# gocupi_0_7_0.net
KiCad netlist of a schematic drawn in EAGLE
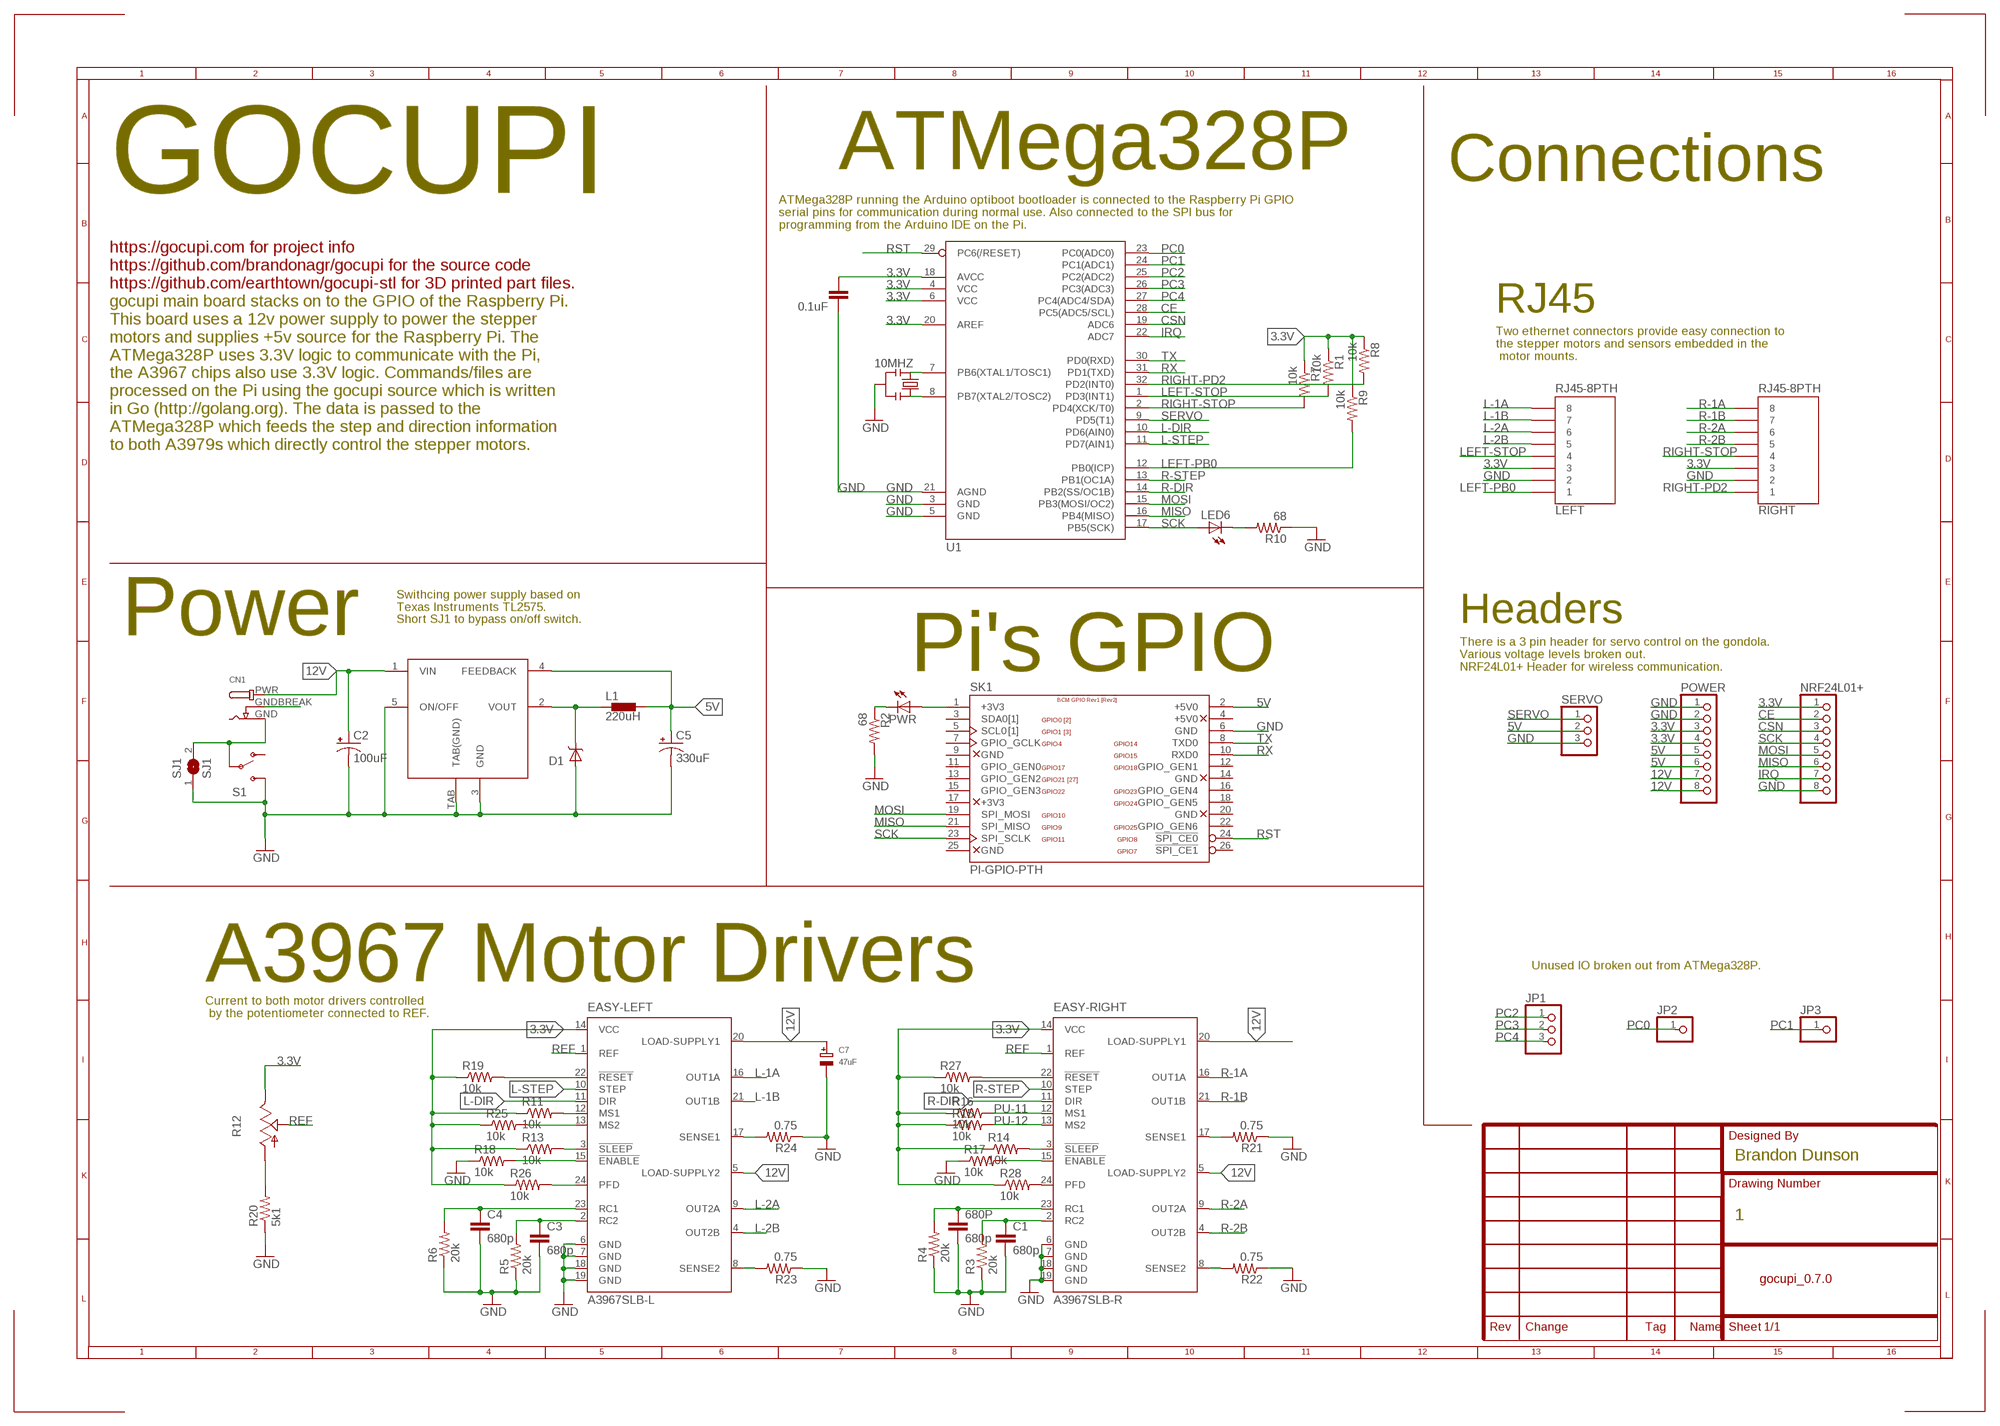
[diagram p0: schematic, sheet 1]

(export (version "E")
  (design (tool "Eeschema 10.0.6"))
  (components
    (comp (ref "10MHZ")
      (value "RESONATORSMD")
      (footprint "eagle-import:RESONATOR-SMD")
      (libsource (lib "eagle-import") (part "RESONATORSMD"))
    )
    (comp (ref "680P")
      (value "680p")
      (footprint "eagle-import:0805")
      (libsource (lib "eagle-import") (part "CAP0805"))
    )
    (comp (ref "C1")
      (value "680p")
      (footprint "eagle-import:0805")
      (libsource (lib "eagle-import") (part "CAP0805"))
    )
    (comp (ref "C2")
      (value "100uF")
      (footprint "eagle-import:PANASONIC_D")
      (libsource (lib "eagle-import") (part "CPOL-USD"))
    )
    (comp (ref "C3")
      (value "680p")
      (footprint "eagle-import:0805")
      (libsource (lib "eagle-import") (part "CAP0805"))
    )
    (comp (ref "C4")
      (value "680p")
      (footprint "eagle-import:0805")
      (libsource (lib "eagle-import") (part "CAP0805"))
    )
    (comp (ref "C5")
      (value "330uF")
      (footprint "eagle-import:PANASONIC_F")
      (libsource (lib "eagle-import") (part "CPOL-USF"))
    )
    (comp (ref "C7")
      (value "47uF")
      (footprint "eagle-import:PANASONIC_C")
      (libsource (lib "eagle-import") (part "CAP_ELECTROLYTICPANASONIC_C"))
    )
    (comp (ref "C8")
      (value "0.1uF")
      (footprint "eagle-import:0805")
      (libsource (lib "eagle-import") (part "CAP0805"))
    )
    (comp (ref "CN1")
      (value "DCBARRELSMT_CORRECT")
      (footprint "eagle-import:DCJACK_2MM_SMT")
      (libsource (lib "eagle-import") (part "DCBARRELSMT_CORRECT"))
    )
    (comp (ref "D1")
      (value "1N5819")
      (footprint "eagle-import:SMA-DIODE")
      (libsource (lib "eagle-import") (part "DIODE-SCHOTTKY_"))
    )
    (comp (ref "EASY-LEFT")
      (value "A3967SLB-L")
      (footprint "eagle-import:SO24W")
      (fields (field (name "MF") "ALLEGRO MICROSYSTEMS, INC.") (field (name "MPN") "A3967SLB-T"))
      (libsource (lib "eagle-import") (part "A3967SLB"))
    )
    (comp (ref "EASY-RIGHT")
      (value "A3967SLB-R")
      (footprint "eagle-import:SO24W")
      (fields (field (name "MF") "ALLEGRO MICROSYSTEMS, INC.") (field (name "MPN") "A3967SLB-T"))
      (libsource (lib "eagle-import") (part "A3967SLB"))
    )
    (comp (ref "JP1")
      (value "PINHD-1X3CB")
      (footprint "eagle-import:1X03-CLEANBIG")
      (libsource (lib "eagle-import") (part "PINHD-1X3CB"))
    )
    (comp (ref "JP2")
      (value "PINHD-1X1CB")
      (footprint "eagle-import:1X01-CLEANBIG")
      (libsource (lib "eagle-import") (part "PINHD-1X1CB"))
    )
    (comp (ref "JP3")
      (value "PINHD-1X1CB")
      (footprint "eagle-import:1X01-CLEANBIG")
      (libsource (lib "eagle-import") (part "PINHD-1X1CB"))
    )
    (comp (ref "L1")
      (value "220uH")
      (footprint "eagle-import:SDR1305")
      (libsource (lib "eagle-import") (part "SDR1305"))
    )
    (comp (ref "LED6")
      (value "LEDCHIPLED_1206")
      (footprint "eagle-import:CHIPLED_1206")
      (libsource (lib "eagle-import") (part "LEDCHIPLED_1206"))
    )
    (comp (ref "LEFT")
      (value "RJ45-8PTH")
      (footprint "eagle-import:RJ45-8")
      (libsource (lib "eagle-import") (part "RJ45-8PTH"))
    )
    (comp (ref "NRF24L01+")
      (value "PINHD-1X8BIG")
      (footprint "eagle-import:1X08-BIG")
      (libsource (lib "eagle-import") (part "PINHD-1X8BIG"))
    )
    (comp (ref "POWER")
      (value "PINHD-1X8CLEANBIG")
      (footprint "eagle-import:1X08-CLEANBIG")
      (libsource (lib "eagle-import") (part "PINHD-1X8CLEANBIG"))
    )
    (comp (ref "PWR")
      (value "LEDCHIPLED_1206")
      (footprint "eagle-import:CHIPLED_1206")
      (libsource (lib "eagle-import") (part "LEDCHIPLED_1206"))
    )
    (comp (ref "R1")
      (value "10k")
      (footprint "eagle-import:0805")
      (libsource (lib "eagle-import") (part "SparkFun-Resistors_RESISTOR0805-RES"))
    )
    (comp (ref "R2")
      (value "68")
      (footprint "eagle-import:0805")
      (libsource (lib "eagle-import") (part "SparkFun-Resistors_RESISTOR0805-RES"))
    )
    (comp (ref "R3")
      (value "20k")
      (footprint "eagle-import:0805")
      (libsource (lib "eagle-import") (part "SparkFun-Resistors_RESISTOR0805-RES"))
    )
    (comp (ref "R4")
      (value "20k")
      (footprint "eagle-import:0805")
      (libsource (lib "eagle-import") (part "SparkFun-Resistors_RESISTOR0805-RES"))
    )
    (comp (ref "R5")
      (value "20k")
      (footprint "eagle-import:0805")
      (libsource (lib "eagle-import") (part "SparkFun-Resistors_RESISTOR0805-RES"))
    )
    (comp (ref "R6")
      (value "20k")
      (footprint "eagle-import:0805")
      (libsource (lib "eagle-import") (part "SparkFun-Resistors_RESISTOR0805-RES"))
    )
    (comp (ref "R7")
      (value "10k")
      (footprint "eagle-import:0805")
      (libsource (lib "eagle-import") (part "SparkFun-Resistors_RESISTOR0805-RES"))
    )
    (comp (ref "R8")
      (value "10k")
      (footprint "eagle-import:0805")
      (libsource (lib "eagle-import") (part "SparkFun-Resistors_RESISTOR0805-RES"))
    )
    (comp (ref "R9")
      (value "10k")
      (footprint "eagle-import:0805")
      (libsource (lib "eagle-import") (part "SparkFun-Resistors_RESISTOR0805-RES"))
    )
    (comp (ref "R10")
      (value "68")
      (footprint "eagle-import:0805")
      (libsource (lib "eagle-import") (part "SparkFun-Resistors_RESISTOR0805-RES"))
    )
    (comp (ref "R11")
      (value "10k")
      (footprint "eagle-import:0805")
      (libsource (lib "eagle-import") (part "SparkFun-Resistors_RESISTOR0805-RES"))
    )
    (comp (ref "R12")
      (value "TRIM_US-SM-42/43A")
      (footprint "eagle-import:SM-42_43A")
      (libsource (lib "eagle-import") (part "TRIM_US-SM-42/43A"))
    )
    (comp (ref "R13")
      (value "10k")
      (footprint "eagle-import:0805")
      (libsource (lib "eagle-import") (part "SparkFun-Resistors_RESISTOR0805-RES"))
    )
    (comp (ref "R14")
      (value "10k")
      (footprint "eagle-import:0805")
      (libsource (lib "eagle-import") (part "SparkFun-Resistors_RESISTOR0805-RES"))
    )
    (comp (ref "R15")
      (value "10k")
      (footprint "eagle-import:0805")
      (libsource (lib "eagle-import") (part "SparkFun-Resistors_RESISTOR0805-RES"))
    )
    (comp (ref "R16")
      (value "10k")
      (footprint "eagle-import:0805")
      (libsource (lib "eagle-import") (part "SparkFun-Resistors_RESISTOR0805-RES"))
    )
    (comp (ref "R17")
      (value "10k")
      (footprint "eagle-import:0805")
      (libsource (lib "eagle-import") (part "SparkFun-Resistors_RESISTOR0805-RES"))
    )
    (comp (ref "R18")
      (value "10k")
      (footprint "eagle-import:0805")
      (libsource (lib "eagle-import") (part "SparkFun-Resistors_RESISTOR0805-RES"))
    )
    (comp (ref "R19")
      (value "10k")
      (footprint "eagle-import:0805")
      (libsource (lib "eagle-import") (part "SparkFun-Resistors_RESISTOR0805-RES"))
    )
    (comp (ref "R20")
      (value "5k1")
      (footprint "eagle-import:0805")
      (libsource (lib "eagle-import") (part "SparkFun-Resistors_RESISTOR0805-RES"))
    )
    (comp (ref "R21")
      (value "0.75")
      (footprint "eagle-import:0805")
      (libsource (lib "eagle-import") (part "SparkFun-Resistors_RESISTOR0805-RES"))
    )
    (comp (ref "R22")
      (value "0.75")
      (footprint "eagle-import:0805")
      (libsource (lib "eagle-import") (part "SparkFun-Resistors_RESISTOR0805-RES"))
    )
    (comp (ref "R23")
      (value "0.75")
      (footprint "eagle-import:0805")
      (libsource (lib "eagle-import") (part "SparkFun-Resistors_RESISTOR0805-RES"))
    )
    (comp (ref "R24")
      (value "0.75")
      (footprint "eagle-import:0805")
      (libsource (lib "eagle-import") (part "SparkFun-Resistors_RESISTOR0805-RES"))
    )
    (comp (ref "R25")
      (value "10k")
      (footprint "eagle-import:0805")
      (libsource (lib "eagle-import") (part "RESISTOR0805-RES"))
    )
    (comp (ref "R26")
      (value "10k")
      (footprint "eagle-import:0805")
      (libsource (lib "eagle-import") (part "SparkFun-Resistors_RESISTOR0805-RES"))
    )
    (comp (ref "R27")
      (value "10k")
      (footprint "eagle-import:0805")
      (libsource (lib "eagle-import") (part "SparkFun-Resistors_RESISTOR0805-RES"))
    )
    (comp (ref "R28")
      (value "10k")
      (footprint "eagle-import:0805")
      (libsource (lib "eagle-import") (part "SparkFun-Resistors_RESISTOR0805-RES"))
    )
    (comp (ref "RIGHT")
      (value "RJ45-8PTH")
      (footprint "eagle-import:RJ45-8")
      (libsource (lib "eagle-import") (part "RJ45-8PTH"))
    )
    (comp (ref "S1")
      (value "SWITCH-SPST-SMD-A")
      (footprint "eagle-import:SWITCH-SPST-SMD-A")
      (libsource (lib "eagle-import") (part "SWITCH-SPST-SMD-A"))
    )
    (comp (ref "SERVO")
      (value "PINHD-1X3")
      (footprint "eagle-import:1X03")
      (libsource (lib "eagle-import") (part "PINHD-1X3"))
    )
    (comp (ref "SJ1")
      (value "SJ1")
      (footprint "eagle-import:SJ")
      (libsource (lib "eagle-import") (part "SJ"))
    )
    (comp (ref "SK1")
      (value "PI-GPIO-PTH")
      (footprint "eagle-import:GPIO-CONNECTOR")
      (libsource (lib "eagle-import") (part "PI-GPIO-PTH"))
    )
    (comp (ref "U$2")
      (value "TL2575")
      (footprint "eagle-import:TO263_5")
      (libsource (lib "eagle-import") (part "TL2575"))
    )
    (comp (ref "U1")
      (value "ATMEGA328_SMT")
      (footprint "eagle-import:TQFP32-08")
      (libsource (lib "eagle-import") (part "ATMEGA328_SMT"))
    )
  )
  (nets
    (net (code "1") (name "/CE") (class "Default")
      (node (ref "NRF24L01+") (pin "2") (pinfunction "2_2") (pintype "passive"))
      (node (ref "U1") (pin "28") (pinfunction "PC5(ADC5/SCL)_28") (pintype "bidirectional"))
    )
    (net (code "2") (name "/CSN") (class "Default")
      (node (ref "NRF24L01+") (pin "3") (pinfunction "3_3") (pintype "passive"))
      (node (ref "U1") (pin "19") (pinfunction "ADC6_19") (pintype "bidirectional"))
    )
    (net (code "3") (name "/IRQ") (class "Default")
      (node (ref "NRF24L01+") (pin "7") (pinfunction "7_7") (pintype "passive"))
      (node (ref "U1") (pin "22") (pinfunction "ADC7_22") (pintype "bidirectional"))
    )
    (net (code "4") (name "/L-1A") (class "Default")
      (node (ref "EASY-LEFT") (pin "16") (pinfunction "OUT1A_16") (pintype "output"))
      (node (ref "LEFT") (pin "8") (pinfunction "8_8") (pintype "bidirectional"))
    )
    (net (code "5") (name "/L-1B") (class "Default")
      (node (ref "EASY-LEFT") (pin "21") (pinfunction "OUT1B_21") (pintype "output"))
      (node (ref "LEFT") (pin "7") (pinfunction "7_7") (pintype "bidirectional"))
    )
    (net (code "6") (name "/L-2A") (class "Default")
      (node (ref "EASY-LEFT") (pin "9") (pinfunction "OUT2A_9") (pintype "output"))
      (node (ref "LEFT") (pin "6") (pinfunction "6_6") (pintype "bidirectional"))
    )
    (net (code "7") (name "/L-2B") (class "Default")
      (node (ref "EASY-LEFT") (pin "4") (pinfunction "OUT2B_4") (pintype "output"))
      (node (ref "LEFT") (pin "5") (pinfunction "5_5") (pintype "bidirectional"))
    )
    (net (code "8") (name "/LEFT-PB0") (class "Default")
      (node (ref "LEFT") (pin "1") (pinfunction "1_1") (pintype "bidirectional"))
      (node (ref "R9") (pin "2") (pinfunction "2_2") (pintype "passive"))
      (node (ref "U1") (pin "12") (pinfunction "PB0(ICP)_12") (pintype "bidirectional"))
    )
    (net (code "9") (name "/LEFT-STOP") (class "Default")
      (node (ref "LEFT") (pin "4") (pinfunction "4_4") (pintype "bidirectional"))
      (node (ref "R1") (pin "2") (pinfunction "2_2") (pintype "passive"))
      (node (ref "U1") (pin "1") (pinfunction "PD3(INT1)_1") (pintype "bidirectional"))
    )
    (net (code "10") (name "/MISO") (class "Default")
      (node (ref "NRF24L01+") (pin "6") (pinfunction "6_6") (pintype "passive"))
      (node (ref "SK1") (pin "21") (pinfunction "SPI_MISO_21") (pintype "bidirectional"))
      (node (ref "U1") (pin "16") (pinfunction "PB4(MISO)_16") (pintype "bidirectional"))
    )
    (net (code "11") (name "/MOSI") (class "Default")
      (node (ref "NRF24L01+") (pin "5") (pinfunction "5_5") (pintype "passive"))
      (node (ref "SK1") (pin "19") (pinfunction "SPI_MOSI_19") (pintype "bidirectional"))
      (node (ref "U1") (pin "15") (pinfunction "PB3(MOSI/OC2)_15") (pintype "bidirectional"))
    )
    (net (code "12") (name "/PC0") (class "Default")
      (node (ref "JP2") (pin "1") (pinfunction "1_1") (pintype "passive"))
      (node (ref "U1") (pin "23") (pinfunction "PC0(ADC0)_23") (pintype "bidirectional"))
    )
    (net (code "13") (name "/PC1") (class "Default")
      (node (ref "JP3") (pin "1") (pinfunction "1_1") (pintype "passive"))
      (node (ref "U1") (pin "24") (pinfunction "PC1(ADC1)_24") (pintype "bidirectional"))
    )
    (net (code "14") (name "/PC2") (class "Default")
      (node (ref "JP1") (pin "1") (pinfunction "1_1") (pintype "passive"))
      (node (ref "U1") (pin "25") (pinfunction "PC2(ADC2)_25") (pintype "bidirectional"))
    )
    (net (code "15") (name "/PC3") (class "Default")
      (node (ref "JP1") (pin "2") (pinfunction "2_2") (pintype "passive"))
      (node (ref "U1") (pin "26") (pinfunction "PC3(ADC3)_26") (pintype "bidirectional"))
    )
    (net (code "16") (name "/PC4") (class "Default")
      (node (ref "JP1") (pin "3") (pinfunction "3_3") (pintype "passive"))
      (node (ref "U1") (pin "27") (pinfunction "PC4(ADC4/SDA)_27") (pintype "bidirectional"))
    )
    (net (code "17") (name "/PU-11") (class "Default")
      (node (ref "EASY-RIGHT") (pin "12") (pinfunction "MS1_12") (pintype "input"))
      (node (ref "R16") (pin "2") (pinfunction "2_2") (pintype "passive"))
    )
    (net (code "18") (name "/PU-12") (class "Default")
      (node (ref "EASY-RIGHT") (pin "13") (pinfunction "MS2_13") (pintype "input"))
      (node (ref "R15") (pin "2") (pinfunction "2_2") (pintype "passive"))
    )
    (net (code "19") (name "/R-1A") (class "Default")
      (node (ref "EASY-RIGHT") (pin "16") (pinfunction "OUT1A_16") (pintype "output"))
      (node (ref "RIGHT") (pin "8") (pinfunction "8_8") (pintype "bidirectional"))
    )
    (net (code "20") (name "/R-1B") (class "Default")
      (node (ref "EASY-RIGHT") (pin "21") (pinfunction "OUT1B_21") (pintype "output"))
      (node (ref "RIGHT") (pin "7") (pinfunction "7_7") (pintype "bidirectional"))
    )
    (net (code "21") (name "/R-2A") (class "Default")
      (node (ref "EASY-RIGHT") (pin "9") (pinfunction "OUT2A_9") (pintype "output"))
      (node (ref "RIGHT") (pin "6") (pinfunction "6_6") (pintype "bidirectional"))
    )
    (net (code "22") (name "/R-2B") (class "Default")
      (node (ref "EASY-RIGHT") (pin "4") (pinfunction "OUT2B_4") (pintype "output"))
      (node (ref "RIGHT") (pin "5") (pinfunction "5_5") (pintype "bidirectional"))
    )
    (net (code "23") (name "/REF") (class "Default")
      (node (ref "EASY-LEFT") (pin "1") (pinfunction "REF_1") (pintype "input"))
      (node (ref "EASY-RIGHT") (pin "1") (pinfunction "REF_1") (pintype "input"))
      (node (ref "R12") (pin "2") (pinfunction "S_2") (pintype "passive"))
    )
    (net (code "24") (name "/RIGHT-PD2") (class "Default")
      (node (ref "R8") (pin "2") (pinfunction "2_2") (pintype "passive"))
      (node (ref "RIGHT") (pin "1") (pinfunction "1_1") (pintype "bidirectional"))
      (node (ref "U1") (pin "32") (pinfunction "PD2(INT0)_32") (pintype "bidirectional"))
    )
    (net (code "25") (name "/RIGHT-STOP") (class "Default")
      (node (ref "R7") (pin "2") (pinfunction "2_2") (pintype "passive"))
      (node (ref "RIGHT") (pin "4") (pinfunction "4_4") (pintype "bidirectional"))
      (node (ref "U1") (pin "2") (pinfunction "PD4(XCK/T0)_2") (pintype "bidirectional"))
    )
    (net (code "26") (name "/RST") (class "Default")
      (node (ref "SK1") (pin "24") (pinfunction "~{SPI_CE0}_24") (pintype "bidirectional"))
      (node (ref "U1") (pin "29") (pinfunction "PC6(/RESET)_29") (pintype "bidirectional"))
    )
    (net (code "27") (name "/RX") (class "Default")
      (node (ref "SK1") (pin "10") (pinfunction "RXD0_10") (pintype "bidirectional"))
      (node (ref "U1") (pin "31") (pinfunction "PD1(TXD)_31") (pintype "bidirectional"))
    )
    (net (code "28") (name "/SCK") (class "Default")
      (node (ref "LED6") (pin "A") (pinfunction "A_A") (pintype "passive"))
      (node (ref "NRF24L01+") (pin "4") (pinfunction "4_4") (pintype "passive"))
      (node (ref "SK1") (pin "23") (pinfunction "SPI_SCLK_23") (pintype "bidirectional"))
      (node (ref "U1") (pin "17") (pinfunction "PB5(SCK)_17") (pintype "bidirectional"))
    )
    (net (code "29") (name "/SERVO") (class "Default")
      (node (ref "SERVO") (pin "1") (pinfunction "1_1") (pintype "passive"))
      (node (ref "U1") (pin "9") (pinfunction "PD5(T1)_9") (pintype "bidirectional"))
    )
    (net (code "30") (name "/TX") (class "Default")
      (node (ref "SK1") (pin "8") (pinfunction "TXD0_8") (pintype "bidirectional"))
      (node (ref "U1") (pin "30") (pinfunction "PD0(RXD)_30") (pintype "bidirectional"))
    )
    (net (code "31") (name "3.3V") (class "Default")
      (node (ref "C8") (pin "1") (pinfunction "1_1") (pintype "passive"))
      (node (ref "EASY-LEFT") (pin "14") (pinfunction "VCC_14") (pintype "power_in"))
      (node (ref "EASY-RIGHT") (pin "14") (pinfunction "VCC_14") (pintype "power_in"))
      (node (ref "LEFT") (pin "3") (pinfunction "3_3") (pintype "bidirectional"))
      (node (ref "NRF24L01+") (pin "1") (pinfunction "1_1") (pintype "passive"))
      (node (ref "POWER") (pin "3") (pinfunction "3_3") (pintype "passive"))
      (node (ref "POWER") (pin "4") (pinfunction "4_4") (pintype "passive"))
      (node (ref "PWR") (pin "A") (pinfunction "A_A") (pintype "passive"))
      (node (ref "R1") (pin "1") (pinfunction "1_1") (pintype "passive"))
      (node (ref "R11") (pin "1") (pinfunction "1_1") (pintype "passive"))
      (node (ref "R12") (pin "3") (pinfunction "E_3") (pintype "passive"))
      (node (ref "R13") (pin "1") (pinfunction "1_1") (pintype "passive"))
      (node (ref "R14") (pin "1") (pinfunction "1_1") (pintype "passive"))
      (node (ref "R15") (pin "1") (pinfunction "1_1") (pintype "passive"))
      (node (ref "R16") (pin "1") (pinfunction "1_1") (pintype "passive"))
      (node (ref "R19") (pin "1") (pinfunction "1_1") (pintype "passive"))
      (node (ref "R25") (pin "1") (pinfunction "1_1") (pintype "passive"))
      (node (ref "R26") (pin "1") (pinfunction "1_1") (pintype "passive"))
      (node (ref "R27") (pin "1") (pinfunction "1_1") (pintype "passive"))
      (node (ref "R28") (pin "1") (pinfunction "1_1") (pintype "passive"))
      (node (ref "R7") (pin "1") (pinfunction "1_1") (pintype "passive"))
      (node (ref "R8") (pin "1") (pinfunction "1_1") (pintype "passive"))
      (node (ref "R9") (pin "1") (pinfunction "1_1") (pintype "passive"))
      (node (ref "RIGHT") (pin "3") (pinfunction "3_3") (pintype "bidirectional"))
      (node (ref "SK1") (pin "1") (pinfunction "+3V3_1") (pintype "power_in"))
      (node (ref "U1") (pin "18") (pinfunction "AVCC_18") (pintype "bidirectional"))
      (node (ref "U1") (pin "20") (pinfunction "AREF_20") (pintype "bidirectional"))
      (node (ref "U1") (pin "4") (pinfunction "VCC_4") (pintype "bidirectional"))
      (node (ref "U1") (pin "6") (pinfunction "VCC_6") (pintype "bidirectional"))
    )
    (net (code "32") (name "5V") (class "Default")
      (node (ref "C5") (pin "+") (pinfunction "+_+") (pintype "passive"))
      (node (ref "L1") (pin "P$2") (pinfunction "2_P$2") (pintype "passive"))
      (node (ref "POWER") (pin "5") (pinfunction "5_5") (pintype "passive"))
      (node (ref "POWER") (pin "6") (pinfunction "6_6") (pintype "passive"))
      (node (ref "SERVO") (pin "2") (pinfunction "2_2") (pintype "passive"))
      (node (ref "SK1") (pin "2") (pinfunction "+5V0_2") (pintype "power_in"))
      (node (ref "U$2") (pin "4") (pinfunction "FEEDBACK_4") (pintype "input"))
    )
    (net (code "33") (name "12V") (class "Default")
      (node (ref "C2") (pin "+") (pinfunction "+_+") (pintype "passive"))
      (node (ref "C7") (pin "+") (pinfunction "+_+") (pintype "passive"))
      (node (ref "CN1") (pin "PWR") (pinfunction "PWR_PWR") (pintype "power_in"))
      (node (ref "EASY-LEFT") (pin "20") (pinfunction "LOAD-SUPPLY1_20") (pintype "input"))
      (node (ref "EASY-LEFT") (pin "5") (pinfunction "LOAD-SUPPLY2_5") (pintype "input"))
      (node (ref "EASY-RIGHT") (pin "20") (pinfunction "LOAD-SUPPLY1_20") (pintype "input"))
      (node (ref "EASY-RIGHT") (pin "5") (pinfunction "LOAD-SUPPLY2_5") (pintype "input"))
      (node (ref "POWER") (pin "7") (pinfunction "7_7") (pintype "passive"))
      (node (ref "POWER") (pin "8") (pinfunction "8_8") (pintype "passive"))
      (node (ref "U$2") (pin "1") (pinfunction "VIN_1") (pintype "input"))
    )
    (net (code "34") (name "GND") (class "Default")
      (node (ref "10MHZ") (pin "2") (pinfunction "2_2") (pintype "passive"))
      (node (ref "680P") (pin "2") (pinfunction "2_2") (pintype "passive"))
      (node (ref "C1") (pin "2") (pinfunction "2_2") (pintype "passive"))
      (node (ref "C2") (pin "-") (pinfunction "-_-") (pintype "passive"))
      (node (ref "C3") (pin "2") (pinfunction "2_2") (pintype "passive"))
      (node (ref "C4") (pin "2") (pinfunction "2_2") (pintype "passive"))
      (node (ref "C5") (pin "-") (pinfunction "-_-") (pintype "passive"))
      (node (ref "C7") (pin "-") (pinfunction "-_-") (pintype "passive"))
      (node (ref "C8") (pin "2") (pinfunction "2_2") (pintype "passive"))
      (node (ref "D1") (pin "A") (pinfunction "A_A") (pintype "passive"))
      (node (ref "EASY-LEFT") (pin "18") (pinfunction "GND_18") (pintype "power_in"))
      (node (ref "EASY-LEFT") (pin "19") (pinfunction "GND_19") (pintype "power_in"))
      (node (ref "EASY-LEFT") (pin "6") (pinfunction "GND_6") (pintype "power_in"))
      (node (ref "EASY-LEFT") (pin "7") (pinfunction "GND_7") (pintype "power_in"))
      (node (ref "EASY-RIGHT") (pin "18") (pinfunction "GND_18") (pintype "power_in"))
      (node (ref "EASY-RIGHT") (pin "19") (pinfunction "GND_19") (pintype "power_in"))
      (node (ref "EASY-RIGHT") (pin "6") (pinfunction "GND_6") (pintype "power_in"))
      (node (ref "EASY-RIGHT") (pin "7") (pinfunction "GND_7") (pintype "power_in"))
      (node (ref "LEFT") (pin "2") (pinfunction "2_2") (pintype "bidirectional"))
      (node (ref "NRF24L01+") (pin "8") (pinfunction "8_8") (pintype "passive"))
      (node (ref "POWER") (pin "1") (pinfunction "1_1") (pintype "passive"))
      (node (ref "POWER") (pin "2") (pinfunction "2_2") (pintype "passive"))
      (node (ref "R10") (pin "1") (pinfunction "1_1") (pintype "passive"))
      (node (ref "R17") (pin "1") (pinfunction "1_1") (pintype "passive"))
      (node (ref "R18") (pin "1") (pinfunction "1_1") (pintype "passive"))
      (node (ref "R2") (pin "2") (pinfunction "2_2") (pintype "passive"))
      (node (ref "R20") (pin "1") (pinfunction "1_1") (pintype "passive"))
      (node (ref "R21") (pin "1") (pinfunction "1_1") (pintype "passive"))
      (node (ref "R22") (pin "1") (pinfunction "1_1") (pintype "passive"))
      (node (ref "R23") (pin "1") (pinfunction "1_1") (pintype "passive"))
      (node (ref "R24") (pin "1") (pinfunction "1_1") (pintype "passive"))
      (node (ref "R3") (pin "1") (pinfunction "1_1") (pintype "passive"))
      (node (ref "R4") (pin "1") (pinfunction "1_1") (pintype "passive"))
      (node (ref "R5") (pin "1") (pinfunction "1_1") (pintype "passive"))
      (node (ref "R6") (pin "1") (pinfunction "1_1") (pintype "passive"))
      (node (ref "RIGHT") (pin "2") (pinfunction "2_2") (pintype "bidirectional"))
      (node (ref "S1") (pin "3") (pinfunction "S_3") (pintype "passive"))
      (node (ref "SERVO") (pin "3") (pinfunction "3_3") (pintype "passive"))
      (node (ref "SJ1") (pin "1") (pinfunction "1_1") (pintype "passive"))
      (node (ref "SK1") (pin "6") (pinfunction "GND_6") (pintype "power_in"))
      (node (ref "U$2") (pin "3") (pinfunction "GND_3") (pintype "power_in"))
      (node (ref "U$2") (pin "5") (pinfunction "ON/OFF_5") (pintype "bidirectional"))
      (node (ref "U$2") (pin "TAB") (pinfunction "TAB(GND)_TAB") (pintype "power_in"))
      (node (ref "U1") (pin "21") (pinfunction "AGND_21") (pintype "bidirectional"))
      (node (ref "U1") (pin "3") (pinfunction "GND_3") (pintype "bidirectional"))
      (node (ref "U1") (pin "5") (pinfunction "GND_5") (pintype "bidirectional"))
    )
    (net (code "35") (name "L-DIR") (class "Default")
      (node (ref "EASY-LEFT") (pin "11") (pinfunction "DIR_11") (pintype "input"))
      (node (ref "U1") (pin "10") (pinfunction "PD6(AIN0)_10") (pintype "bidirectional"))
    )
    (net (code "36") (name "L-STEP") (class "Default")
      (node (ref "EASY-LEFT") (pin "10") (pinfunction "STEP_10") (pintype "input"))
      (node (ref "U1") (pin "11") (pinfunction "PD7(AIN1)_11") (pintype "bidirectional"))
    )
    (net (code "37") (name "Net-(EASY-LEFT-MS1)") (class "Default")
      (node (ref "EASY-LEFT") (pin "12") (pinfunction "MS1_12") (pintype "input"))
      (node (ref "R11") (pin "2") (pinfunction "2_2") (pintype "passive"))
    )
    (net (code "38") (name "Net-(EASY-LEFT-MS2)") (class "Default")
      (node (ref "EASY-LEFT") (pin "13") (pinfunction "MS2_13") (pintype "input"))
      (node (ref "R25") (pin "2") (pinfunction "2_2") (pintype "passive"))
    )
    (net (code "39") (name "Net-(EASY-LEFT-PFD)") (class "Default")
      (node (ref "EASY-LEFT") (pin "24") (pinfunction "PFD_24") (pintype "input"))
      (node (ref "R26") (pin "2") (pinfunction "2_2") (pintype "passive"))
    )
    (net (code "40") (name "Net-(EASY-LEFT-RC1)") (class "Default")
      (node (ref "C4") (pin "1") (pinfunction "1_1") (pintype "passive"))
      (node (ref "EASY-LEFT") (pin "23") (pinfunction "RC1_23") (pintype "input"))
      (node (ref "R6") (pin "2") (pinfunction "2_2") (pintype "passive"))
    )
    (net (code "41") (name "Net-(EASY-LEFT-RC2)") (class "Default")
      (node (ref "C3") (pin "1") (pinfunction "1_1") (pintype "passive"))
      (node (ref "EASY-LEFT") (pin "2") (pinfunction "RC2_2") (pintype "input"))
      (node (ref "R5") (pin "2") (pinfunction "2_2") (pintype "passive"))
    )
    (net (code "42") (name "Net-(EASY-LEFT-SENSE1)") (class "Default")
      (node (ref "EASY-LEFT") (pin "17") (pinfunction "SENSE1_17") (pintype "input"))
      (node (ref "R24") (pin "2") (pinfunction "2_2") (pintype "passive"))
    )
    (net (code "43") (name "Net-(EASY-LEFT-SENSE2)") (class "Default")
      (node (ref "EASY-LEFT") (pin "8") (pinfunction "SENSE2_8") (pintype "input"))
      (node (ref "R23") (pin "2") (pinfunction "2_2") (pintype "passive"))
    )
    (net (code "44") (name "Net-(EASY-LEFT-~{ENABLE})") (class "Default")
      (node (ref "EASY-LEFT") (pin "15") (pinfunction "~{ENABLE}_15") (pintype "input"))
      (node (ref "R18") (pin "2") (pinfunction "2_2") (pintype "passive"))
    )
    (net (code "45") (name "Net-(EASY-LEFT-~{RESET})") (class "Default")
      (node (ref "EASY-LEFT") (pin "22") (pinfunction "~{RESET}_22") (pintype "input"))
      (node (ref "R19") (pin "2") (pinfunction "2_2") (pintype "passive"))
    )
    (net (code "46") (name "Net-(EASY-LEFT-~{SLEEP})") (class "Default")
      (node (ref "EASY-LEFT") (pin "3") (pinfunction "~{SLEEP}_3") (pintype "input"))
      (node (ref "R13") (pin "2") (pinfunction "2_2") (pintype "passive"))
    )
    (net (code "47") (name "Net-(EASY-RIGHT-PFD)") (class "Default")
      (node (ref "EASY-RIGHT") (pin "24") (pinfunction "PFD_24") (pintype "input"))
      (node (ref "R28") (pin "2") (pinfunction "2_2") (pintype "passive"))
    )
    (net (code "48") (name "Net-(EASY-RIGHT-RC1)") (class "Default")
      (node (ref "680P") (pin "1") (pinfunction "1_1") (pintype "passive"))
      (node (ref "EASY-RIGHT") (pin "23") (pinfunction "RC1_23") (pintype "input"))
      (node (ref "R4") (pin "2") (pinfunction "2_2") (pintype "passive"))
    )
    (net (code "49") (name "Net-(EASY-RIGHT-RC2)") (class "Default")
      (node (ref "C1") (pin "1") (pinfunction "1_1") (pintype "passive"))
      (node (ref "EASY-RIGHT") (pin "2") (pinfunction "RC2_2") (pintype "input"))
      (node (ref "R3") (pin "2") (pinfunction "2_2") (pintype "passive"))
    )
    (net (code "50") (name "Net-(EASY-RIGHT-SENSE1)") (class "Default")
      (node (ref "EASY-RIGHT") (pin "17") (pinfunction "SENSE1_17") (pintype "input"))
      (node (ref "R21") (pin "2") (pinfunction "2_2") (pintype "passive"))
    )
    (net (code "51") (name "Net-(EASY-RIGHT-SENSE2)") (class "Default")
      (node (ref "EASY-RIGHT") (pin "8") (pinfunction "SENSE2_8") (pintype "input"))
      (node (ref "R22") (pin "2") (pinfunction "2_2") (pintype "passive"))
    )
    (net (code "52") (name "Net-(EASY-RIGHT-~{ENABLE})") (class "Default")
      (node (ref "EASY-RIGHT") (pin "15") (pinfunction "~{ENABLE}_15") (pintype "input"))
      (node (ref "R17") (pin "2") (pinfunction "2_2") (pintype "passive"))
    )
    (net (code "53") (name "Net-(EASY-RIGHT-~{RESET})") (class "Default")
      (node (ref "EASY-RIGHT") (pin "22") (pinfunction "~{RESET}_22") (pintype "input"))
      (node (ref "R27") (pin "2") (pinfunction "2_2") (pintype "passive"))
    )
    (net (code "54") (name "Net-(EASY-RIGHT-~{SLEEP})") (class "Default")
      (node (ref "EASY-RIGHT") (pin "3") (pinfunction "~{SLEEP}_3") (pintype "input"))
      (node (ref "R14") (pin "2") (pinfunction "2_2") (pintype "passive"))
    )
    (net (code "55") (name "Net-(L1-1)") (class "Default")
      (node (ref "D1") (pin "C") (pinfunction "C_C") (pintype "passive"))
      (node (ref "L1") (pin "P$1") (pinfunction "1_P$1") (pintype "passive"))
      (node (ref "U$2") (pin "2") (pinfunction "VOUT_2") (pintype "output"))
    )
    (net (code "56") (name "Net-(LED6-PadC)") (class "Default")
      (node (ref "LED6") (pin "C") (pinfunction "C_C") (pintype "passive"))
      (node (ref "R10") (pin "2") (pinfunction "2_2") (pintype "passive"))
    )
    (net (code "57") (name "Net-(PWR-PadC)") (class "Default")
      (node (ref "PWR") (pin "C") (pinfunction "C_C") (pintype "passive"))
      (node (ref "R2") (pin "1") (pinfunction "1_1") (pintype "passive"))
    )
    (net (code "58") (name "Net-(R12-A)") (class "Default")
      (node (ref "R12") (pin "1") (pinfunction "A_1") (pintype "passive"))
      (node (ref "R20") (pin "2") (pinfunction "2_2") (pintype "passive"))
    )
    (net (code "59") (name "Net-(S1-P)") (class "Default")
      (node (ref "CN1") (pin "GND") (pinfunction "GND_GND") (pintype "power_in"))
      (node (ref "S1") (pin "2") (pinfunction "P_2") (pintype "passive"))
      (node (ref "SJ1") (pin "2") (pinfunction "2_2") (pintype "passive"))
    )
    (net (code "60") (name "Net-(U1-PB6(XTAL1{slash}TOSC1))") (class "Default")
      (node (ref "10MHZ") (pin "1") (pinfunction "1_1") (pintype "passive"))
      (node (ref "U1") (pin "7") (pinfunction "PB6(XTAL1/TOSC1)_7") (pintype "bidirectional"))
    )
    (net (code "61") (name "Net-(U1-PB7(XTAL2{slash}TOSC2))") (class "Default")
      (node (ref "10MHZ") (pin "3") (pinfunction "3_3") (pintype "passive"))
      (node (ref "U1") (pin "8") (pinfunction "PB7(XTAL2/TOSC2)_8") (pintype "bidirectional"))
    )
    (net (code "62") (name "R-DIR") (class "Default")
      (node (ref "EASY-RIGHT") (pin "11") (pinfunction "DIR_11") (pintype "input"))
      (node (ref "U1") (pin "14") (pinfunction "PB2(SS/OC1B)_14") (pintype "bidirectional"))
    )
    (net (code "63") (name "R-STEP") (class "Default")
      (node (ref "EASY-RIGHT") (pin "10") (pinfunction "STEP_10") (pintype "input"))
      (node (ref "U1") (pin "13") (pinfunction "PB1(OC1A)_13") (pintype "bidirectional"))
    )
    (net (code "64") (name "unconnected-(CN1-PadGNDBREAK)") (class "Default")
      (node (ref "CN1") (pin "GNDBREAK") (pinfunction "GNDBREAK_GNDBREAK") (pintype "power_in"))
    )
    (net (code "65") (name "unconnected-(S1-O-Pad1)") (class "Default")
      (node (ref "S1") (pin "1") (pinfunction "O_1") (pintype "passive"))
    )
    (net (code "66") (name "unconnected-(SK1-+3V3-Pad17)") (class "Default")
      (node (ref "SK1") (pin "17") (pinfunction "+3V3_17") (pintype "no_connect"))
    )
    (net (code "67") (name "unconnected-(SK1-+5V0-Pad4)") (class "Default")
      (node (ref "SK1") (pin "4") (pinfunction "+5V0_4") (pintype "no_connect"))
    )
    (net (code "68") (name "unconnected-(SK1-GND-Pad9)") (class "Default")
      (node (ref "SK1") (pin "9") (pinfunction "GND_9") (pintype "no_connect"))
    )
    (net (code "69") (name "unconnected-(SK1-GND-Pad14)") (class "Default")
      (node (ref "SK1") (pin "14") (pinfunction "GND_14") (pintype "no_connect"))
    )
    (net (code "70") (name "unconnected-(SK1-GND-Pad20)") (class "Default")
      (node (ref "SK1") (pin "20") (pinfunction "GND_20") (pintype "no_connect"))
    )
    (net (code "71") (name "unconnected-(SK1-GND-Pad25)") (class "Default")
      (node (ref "SK1") (pin "25") (pinfunction "GND_25") (pintype "no_connect"))
    )
    (net (code "72") (name "unconnected-(SK1-GPIO_GCLK-Pad7)") (class "Default")
      (node (ref "SK1") (pin "7") (pinfunction "GPIO_GCLK_7") (pintype "bidirectional"))
    )
    (net (code "73") (name "unconnected-(SK1-GPIO_GEN0-Pad11)") (class "Default")
      (node (ref "SK1") (pin "11") (pinfunction "GPIO_GEN0_11") (pintype "bidirectional"))
    )
    (net (code "74") (name "unconnected-(SK1-GPIO_GEN1-Pad12)") (class "Default")
      (node (ref "SK1") (pin "12") (pinfunction "GPIO_GEN1_12") (pintype "bidirectional"))
    )
    (net (code "75") (name "unconnected-(SK1-GPIO_GEN2-Pad13)") (class "Default")
      (node (ref "SK1") (pin "13") (pinfunction "GPIO_GEN2_13") (pintype "bidirectional"))
    )
    (net (code "76") (name "unconnected-(SK1-GPIO_GEN3-Pad15)") (class "Default")
      (node (ref "SK1") (pin "15") (pinfunction "GPIO_GEN3_15") (pintype "bidirectional"))
    )
    (net (code "77") (name "unconnected-(SK1-GPIO_GEN4-Pad16)") (class "Default")
      (node (ref "SK1") (pin "16") (pinfunction "GPIO_GEN4_16") (pintype "bidirectional"))
    )
    (net (code "78") (name "unconnected-(SK1-GPIO_GEN5-Pad18)") (class "Default")
      (node (ref "SK1") (pin "18") (pinfunction "GPIO_GEN5_18") (pintype "bidirectional"))
    )
    (net (code "79") (name "unconnected-(SK1-GPIO_GEN6-Pad22)") (class "Default")
      (node (ref "SK1") (pin "22") (pinfunction "GPIO_GEN6_22") (pintype "bidirectional"))
    )
    (net (code "80") (name "unconnected-(SK1-SCL0-Pad5)") (class "Default")
      (node (ref "SK1") (pin "5") (pinfunction "SCL0_5") (pintype "bidirectional"))
    )
    (net (code "81") (name "unconnected-(SK1-SDA0-Pad3)") (class "Default")
      (node (ref "SK1") (pin "3") (pinfunction "SDA0_3") (pintype "bidirectional"))
    )
    (net (code "82") (name "unconnected-(SK1-~{SPI_CE1}-Pad26)") (class "Default")
      (node (ref "SK1") (pin "26") (pinfunction "~{SPI_CE1}_26") (pintype "bidirectional"))
    )
  )
)
